# dual_power_supply.net
KiCad netlist of a schematic drawn in EAGLE
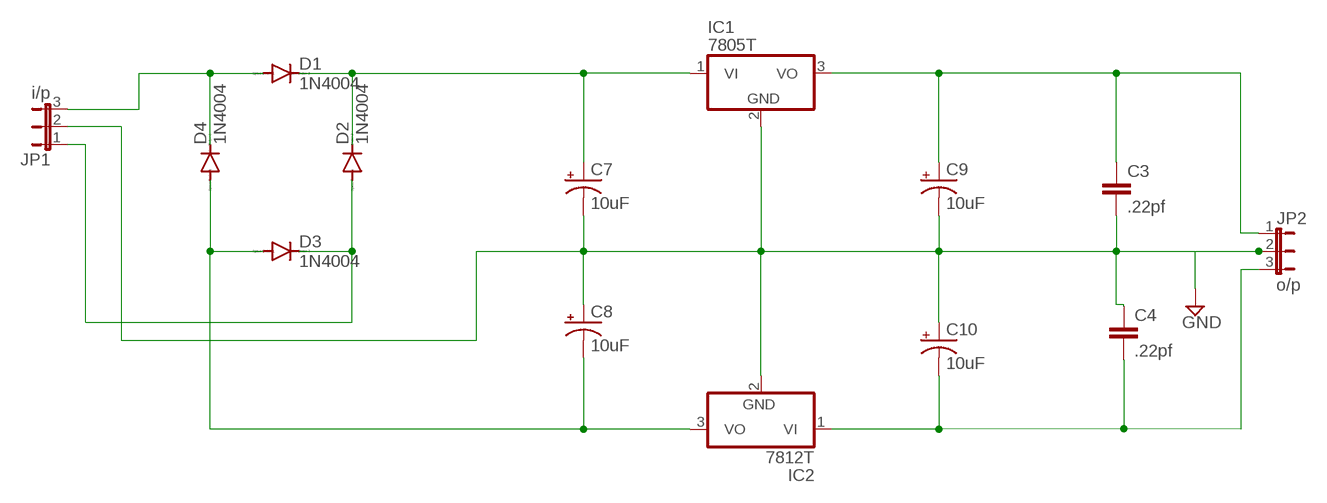
[diagram p0: schematic, sheet 1]

(export (version "E")
  (design (tool "Eeschema 10.0.6"))
  (components
    (comp (ref "C3")
      (value ".22pf")
      (footprint "eagle-import:C2.5-3")
      (libsource (lib "eagle-import") (part "C2,5-3"))
    )
    (comp (ref "C4")
      (value ".22pf")
      (footprint "eagle-import:C2.5-3")
      (libsource (lib "eagle-import") (part "C2,5-3"))
    )
    (comp (ref "C7")
      (value "10uF")
      (footprint "eagle-import:E3,5-8")
      (libsource (lib "eagle-import") (part "CPOL-USE3.5-8"))
    )
    (comp (ref "C8")
      (value "10uF")
      (footprint "eagle-import:E3,5-8")
      (libsource (lib "eagle-import") (part "CPOL-USE3.5-8"))
    )
    (comp (ref "C9")
      (value "10uF")
      (footprint "eagle-import:E3,5-8")
      (libsource (lib "eagle-import") (part "CPOL-USE3.5-8"))
    )
    (comp (ref "C10")
      (value "10uF")
      (footprint "eagle-import:E3,5-8")
      (libsource (lib "eagle-import") (part "CPOL-USE3.5-8"))
    )
    (comp (ref "D1")
      (value "1N4004")
      (footprint "eagle-import:DO41-10")
      (libsource (lib "eagle-import") (part "1N4004"))
    )
    (comp (ref "D2")
      (value "1N4004")
      (footprint "eagle-import:DO41-10")
      (libsource (lib "eagle-import") (part "1N4004"))
    )
    (comp (ref "D3")
      (value "1N4004")
      (footprint "eagle-import:DO41-10")
      (libsource (lib "eagle-import") (part "1N4004"))
    )
    (comp (ref "D4")
      (value "1N4004")
      (footprint "eagle-import:DO41-10")
      (libsource (lib "eagle-import") (part "1N4004"))
    )
    (comp (ref "IC1")
      (value "7805T")
      (footprint "eagle-import:TO220H")
      (libsource (lib "eagle-import") (part "78T05"))
    )
    (comp (ref "IC2")
      (value "7812T")
      (footprint "eagle-import:TO220H")
      (libsource (lib "eagle-import") (part "78T12"))
    )
    (comp (ref "JP1")
      (value "i/p")
      (footprint "eagle-import:JP2")
      (libsource (lib "eagle-import") (part "JP2E"))
    )
    (comp (ref "JP2")
      (value "o/p")
      (footprint "eagle-import:JP2")
      (libsource (lib "eagle-import") (part "JP2E"))
    )
  )
  (nets
    (net (code "1") (name "GND") (class "Default")
      (node (ref "C10") (pin "+") (pinfunction "+_+") (pintype "passive"))
      (node (ref "C3") (pin "2") (pinfunction "2_2") (pintype "passive"))
      (node (ref "C4") (pin "1") (pinfunction "1_1") (pintype "passive"))
      (node (ref "C7") (pin "-") (pinfunction "-_-") (pintype "passive"))
      (node (ref "C8") (pin "+") (pinfunction "+_+") (pintype "passive"))
      (node (ref "C9") (pin "-") (pinfunction "-_-") (pintype "passive"))
      (node (ref "IC1") (pin "2") (pinfunction "GND_2") (pintype "passive"))
      (node (ref "IC2") (pin "2") (pinfunction "GND_2") (pintype "passive"))
      (node (ref "JP1") (pin "2") (pinfunction "2_2") (pintype "passive"))
      (node (ref "JP2") (pin "2") (pinfunction "2_2") (pintype "passive"))
    )
    (net (code "2") (name "Net-(D1-PadA)") (class "Default")
      (node (ref "D1") (pin "A") (pinfunction "A_A") (pintype "passive"))
      (node (ref "D4") (pin "C") (pinfunction "C_C") (pintype "passive"))
      (node (ref "JP1") (pin "3") (pinfunction "3_3") (pintype "passive"))
    )
    (net (code "3") (name "Net-(D2-PadA)") (class "Default")
      (node (ref "D2") (pin "A") (pinfunction "A_A") (pintype "passive"))
      (node (ref "D3") (pin "C") (pinfunction "C_C") (pintype "passive"))
      (node (ref "JP1") (pin "1") (pinfunction "1_1") (pintype "passive"))
    )
    (net (code "4") (name "Net-(IC1-VI)") (class "Default")
      (node (ref "C7") (pin "+") (pinfunction "+_+") (pintype "passive"))
      (node (ref "D1") (pin "C") (pinfunction "C_C") (pintype "passive"))
      (node (ref "D2") (pin "C") (pinfunction "C_C") (pintype "passive"))
      (node (ref "IC1") (pin "1") (pinfunction "VI_1") (pintype "input"))
    )
    (net (code "5") (name "Net-(IC1-VO)") (class "Default")
      (node (ref "C3") (pin "1") (pinfunction "1_1") (pintype "passive"))
      (node (ref "C9") (pin "+") (pinfunction "+_+") (pintype "passive"))
      (node (ref "IC1") (pin "3") (pinfunction "VO_3") (pintype "passive"))
      (node (ref "JP2") (pin "1") (pinfunction "1_1") (pintype "passive"))
    )
    (net (code "6") (name "Net-(IC2-VI)") (class "Default")
      (node (ref "C10") (pin "-") (pinfunction "-_-") (pintype "passive"))
      (node (ref "C4") (pin "2") (pinfunction "2_2") (pintype "passive"))
      (node (ref "IC2") (pin "1") (pinfunction "VI_1") (pintype "input"))
      (node (ref "JP2") (pin "3") (pinfunction "3_3") (pintype "passive"))
    )
    (net (code "7") (name "Net-(IC2-VO)") (class "Default")
      (node (ref "C8") (pin "-") (pinfunction "-_-") (pintype "passive"))
      (node (ref "D3") (pin "A") (pinfunction "A_A") (pintype "passive"))
      (node (ref "D4") (pin "A") (pinfunction "A_A") (pintype "passive"))
      (node (ref "IC2") (pin "3") (pinfunction "VO_3") (pintype "passive"))
    )
  )
)
